# GPSclock.net
KiCad netlist of a schematic drawn in EasyEDA Pro
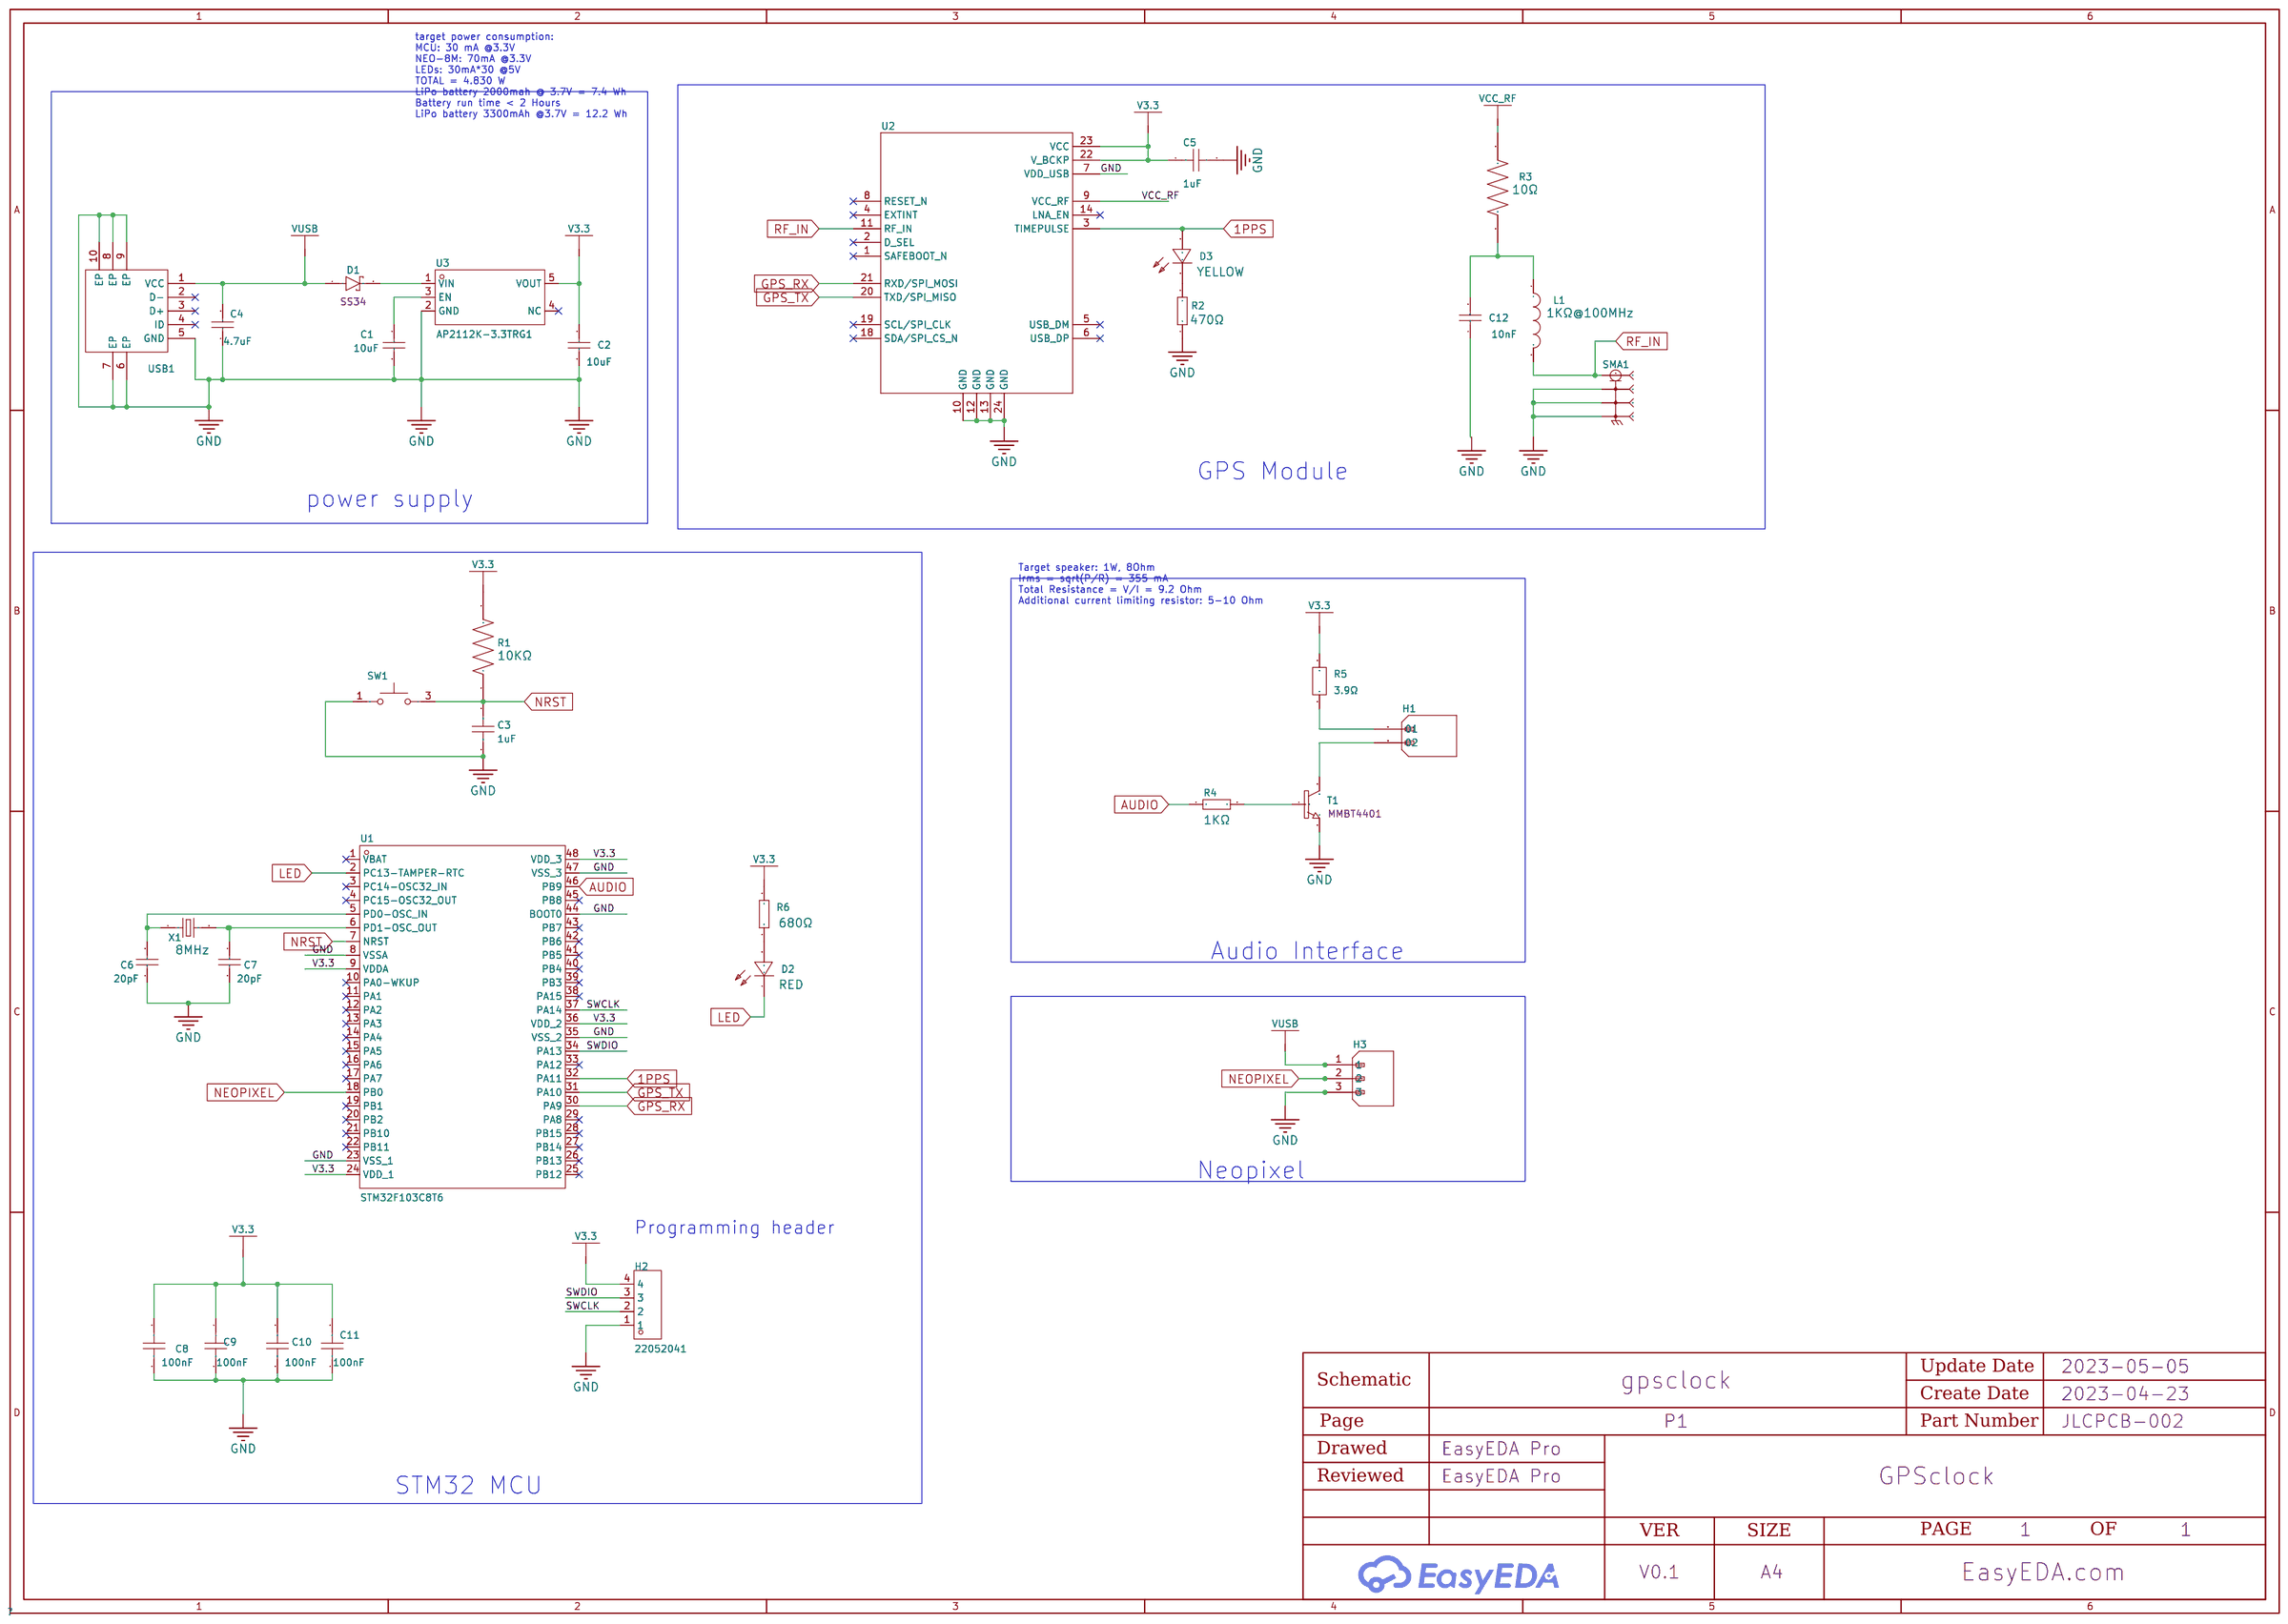
[diagram p0: schematic sheet]

(export (version "E")
  (design (tool "Eeschema 10.0.6"))
  (components
    (comp (ref "C1")
      (value "10uF")
      (footprint "easyedapro:C1206")
      (fields
        (field (name "Manufacturer Part") "CL31A106KBHNNNE")
        (field (name "Manufacturer") "SAMSUNG(三星)")
      )
      (libsource (lib "easyedapro") (part "CL31A106KBHNNNE"))
    )
    (comp (ref "C2")
      (value "10uF")
      (footprint "easyedapro:C1206")
      (fields
        (field (name "Manufacturer Part") "CL31A106KBHNNNE")
        (field (name "Manufacturer") "SAMSUNG(三星)")
      )
      (libsource (lib "easyedapro") (part "CL31A106KBHNNNE"))
    )
    (comp (ref "C3")
      (value "1uF")
      (footprint "easyedapro:C1206")
      (fields
        (field (name "Manufacturer Part") "CL31B105KBHNNNE")
        (field (name "Manufacturer") "SAMSUNG(三星)")
        (field (name "Tolerance") "±10%")
      )
      (libsource (lib "easyedapro") (part "CL31B105KBHNNNE"))
    )
    (comp (ref "C4")
      (value "4.7uF")
      (footprint "easyedapro:C0603")
      (fields
        (field (name "Manufacturer Part") "CL10A475KO8NNNC")
        (field (name "Manufacturer") "SAMSUNG(三星)")
        (field (name "Tolerance") "±10%")
      )
      (libsource (lib "easyedapro") (part "CL10A475KO8NNNC"))
    )
    (comp (ref "C5")
      (value "1uF")
      (footprint "easyedapro:C1206")
      (fields
        (field (name "Manufacturer Part") "CL31B105KBHNNNE")
        (field (name "Manufacturer") "SAMSUNG(三星)")
        (field (name "Tolerance") "±10%")
      )
      (libsource (lib "easyedapro") (part "CL31B105KBHNNNE"))
    )
    (comp (ref "C6")
      (value "20pF")
      (footprint "easyedapro:C0603")
      (fields
        (field (name "Manufacturer Part") "CL10C200JB8NNNC")
        (field (name "Manufacturer") "SAMSUNG(三星)")
        (field (name "Tolerance") "±5%")
      )
      (libsource (lib "easyedapro") (part "CL10C200JB8NNNC"))
    )
    (comp (ref "C7")
      (value "20pF")
      (footprint "easyedapro:C0603")
      (fields
        (field (name "Manufacturer Part") "CL10C200JB8NNNC")
        (field (name "Manufacturer") "SAMSUNG(三星)")
        (field (name "Tolerance") "±5%")
      )
      (libsource (lib "easyedapro") (part "CL10C200JB8NNNC"))
    )
    (comp (ref "C8")
      (value "100nF")
      (footprint "easyedapro:C0603")
      (fields
        (field (name "Manufacturer Part") "CC0603KRX7R9BB104")
        (field (name "Manufacturer") "YAGEO(国巨)")
        (field (name "Tolerance") "±10%")
      )
      (libsource (lib "easyedapro") (part "CC0603KRX7R9BB104"))
    )
    (comp (ref "C9")
      (value "100nF")
      (footprint "easyedapro:C0603")
      (fields
        (field (name "Manufacturer Part") "CC0603KRX7R9BB104")
        (field (name "Manufacturer") "YAGEO(国巨)")
        (field (name "Tolerance") "±10%")
      )
      (libsource (lib "easyedapro") (part "CC0603KRX7R9BB104"))
    )
    (comp (ref "C10")
      (value "100nF")
      (footprint "easyedapro:C0603")
      (fields
        (field (name "Manufacturer Part") "CC0603KRX7R9BB104")
        (field (name "Manufacturer") "YAGEO(国巨)")
        (field (name "Tolerance") "±10%")
      )
      (libsource (lib "easyedapro") (part "CC0603KRX7R9BB104"))
    )
    (comp (ref "C11")
      (value "100nF")
      (footprint "easyedapro:C0603")
      (fields
        (field (name "Manufacturer Part") "CC0603KRX7R9BB104")
        (field (name "Manufacturer") "YAGEO(国巨)")
        (field (name "Tolerance") "±10%")
      )
      (libsource (lib "easyedapro") (part "CC0603KRX7R9BB104"))
    )
    (comp (ref "C12")
      (value "10nF")
      (footprint "easyedapro:C0805")
      (fields
        (field (name "Manufacturer Part") "CL21B103KBANNNC")
        (field (name "Manufacturer") "SAMSUNG(三星)")
        (field (name "Tolerance") "±10%")
      )
      (libsource (lib "easyedapro") (part "CL21B103KBANNNC"))
    )
    (comp (ref "D1")
      (value "~")
      (footprint "easyedapro:SODFL3718X102N")
      (description "SS34")
      (fields
        (field (name "Manufacturer Part") "SS34LWH")
        (field (name "Manufacturer") "Taiwan Semiconductor Corporation")
      )
      (libsource (lib "easyedapro") (part "SS34LWH_"))
    )
    (comp (ref "D2")
      (value "RED")
      (footprint "easyedapro:LED_APHD1608LVBC/D")
      (fields (field (name "Manufacturer Part") "APTD1608LSURCK") (field (name "Manufacturer") "Kingbright"))
      (libsource (lib "easyedapro") (part "APTD1608LSURCK"))
    )
    (comp (ref "D3")
      (value "YELLOW")
      (footprint "easyedapro:LED_APHD1608LVBC/D")
      (fields (field (name "Manufacturer Part") "APTD1608LSYCK") (field (name "Manufacturer") "Kingbright"))
      (libsource (lib "easyedapro") (part "APTD1608LSYCK"))
    )
    (comp (ref "H1")
      (value "~")
      (footprint "easyedapro:WURTH_61300211121")
      (fields
        (field (name "Manufacturer Part") "61300211121")
        (field (name "Manufacturer") "Würth Elektronik")
      )
      (libsource (lib "easyedapro") (part "61300211121_"))
    )
    (comp (ref "H2")
      (value "22052041")
      (footprint "easyedapro:HDR-TH_4P-P2.54-H-M-W9.5")
      (fields (field (name "Manufacturer") "MOLEX"))
      (libsource (lib "easyedapro") (part "22052041"))
    )
    (comp (ref "H3")
      (value "~")
      (footprint "easyedapro:AMPHENOL_G800W305018EU")
      (fields (field (name "Manufacturer Part") "G800W305018EU") (field (name "Manufacturer") "AMPHENOL"))
      (libsource (lib "easyedapro") (part "G800W305018EU_"))
    )
    (comp (ref "L1")
      (value "1KΩ@100MHz")
      (footprint "easyedapro:BEADC1005X55N")
      (fields
        (field (name "Manufacturer Part") "BLM15HG102BH1D")
        (field (name "Manufacturer") "Murata Electronics")
      )
      (libsource (lib "easyedapro") (part "BLM15HG102BH1D_"))
    )
    (comp (ref "R1")
      (value "10KΩ")
      (footprint "easyedapro:RES_ERA8AEB103V")
      (libsource (lib "easyedapro") (part "ERA8AEB103V_"))
    )
    (comp (ref "R2")
      (value "470Ω")
      (footprint "easyedapro:R0603_NEW")
      (fields (field (name "Manufacturer Part") "RC0603FR-13470RL") (field (name "Manufacturer") "YAGEO"))
      (libsource (lib "easyedapro") (part "RC0603FR-13470RL_"))
    )
    (comp (ref "R3")
      (value "10Ω")
      (footprint "easyedapro:RESC2012X60N")
      (fields (field (name "Manufacturer Part") "SR0805FR-4710RL") (field (name "Manufacturer") "YAGEO"))
      (libsource (lib "easyedapro") (part "SR0805FR-4710RL_"))
    )
    (comp (ref "R4")
      (value "1KΩ")
      (footprint "easyedapro:0603")
      (fields (field (name "Manufacturer Part") "RC0603FR-101KL") (field (name "Manufacturer") "YAGEO"))
      (libsource (lib "easyedapro") (part "RC0603FR-101KL_"))
    )
    (comp (ref "R5")
      (value "3.9Ω")
      (footprint "easyedapro:RES-TH_BD4.5-L11.5-P15.50-D0.8")
      (fields
        (field (name "Manufacturer Part") "RSF100JR-73-3R9")
        (field (name "Manufacturer") "YAGEO(国巨)")
        (field (name "Tolerance") "±5%")
      )
      (libsource (lib "easyedapro") (part "RSF100JR-73-3R9"))
    )
    (comp (ref "R6")
      (value "680Ω")
      (footprint "easyedapro:0603")
      (fields (field (name "Manufacturer Part") "RC0603FR-13680RL") (field (name "Manufacturer") "YAGEO"))
      (libsource (lib "easyedapro") (part "RC0603FR-13680RL_"))
    )
    (comp (ref "SMA1")
      (value "~")
      (footprint "easyedapro:MOLEX_0734120110")
      (fields (field (name "Manufacturer Part") "0734120110") (field (name "Manufacturer") "MOLEX"))
      (libsource (lib "easyedapro") (part "0734120110_"))
    )
    (comp (ref "SW1")
      (value "~")
      (footprint "easyedapro:SW_800SP9B6M6RE")
      (fields (field (name "Manufacturer Part") "800SP9B6M6RE") (field (name "Manufacturer") "E-Switch"))
      (libsource (lib "easyedapro") (part "800SP9B6M6RE_"))
    )
    (comp (ref "T1")
      (value "~")
      (footprint "easyedapro:TRANS_MMBT4401")
      (description "MMBT4401")
      (fields
        (field (name "Manufacturer Part") "4530-MMBT4401CT-ND")
        (field (name "Manufacturer") "ANBON SEMICONDUCTOR LIMITED")
      )
      (libsource (lib "easyedapro") (part "MMBT4401_"))
    )
    (comp (ref "U1")
      (value "STM32F103C8T6")
      (footprint "easyedapro:LQFP-48_L7.0-W7.0-P0.50-LS9.0-BL")
      (fields (field (name "Manufacturer") "ST(意法半导体)"))
      (libsource (lib "easyedapro") (part "STM32F103C8T6"))
    )
    (comp (ref "U2")
      (value "~")
      (footprint "easyedapro:XCVR_NEO-M8N-0")
      (fields (field (name "Manufacturer Part") "NEO-M8N-0") (field (name "Manufacturer") "U-BLOX"))
      (libsource (lib "easyedapro") (part "NEO-M8N-0_"))
    )
    (comp (ref "U3")
      (value "AP2112K-3.3TRG1")
      (footprint "easyedapro:SOT-25-5_L2.9-W1.6-P0.95-LS2.8-BL")
      (fields (field (name "Manufacturer") "DIODES(美台)"))
      (libsource (lib "easyedapro") (part "AP2112K-3.3TRG1"))
    )
    (comp (ref "USB1")
      (value "1050170001")
      (footprint "easyedapro:MICRO-USB-SMD_105017-0001")
      (fields (field (name "Manufacturer") "MOLEX"))
      (libsource (lib "easyedapro") (part "105017-0001"))
    )
    (comp (ref "X1")
      (value "8MHz")
      (fields (field (name "Manufacturer Part") "ECS-80-18-5PX-TR") (field (name "Manufacturer") "ECS inc"))
      (libsource (lib "easyedapro") (part "ECS-80-18-5PX-TR_"))
    )
  )
  (nets
    (net (code "1") (name "/SWCLK") (class "Default")
      (node (ref "H2") (pin "2") (pinfunction "2_2") (pintype "input"))
      (node (ref "U1") (pin "37") (pinfunction "PA14_37") (pintype "input"))
    )
    (net (code "2") (name "/SWDIO") (class "Default")
      (node (ref "H2") (pin "3") (pinfunction "3_3") (pintype "input"))
      (node (ref "U1") (pin "34") (pinfunction "PA13_34") (pintype "input"))
    )
    (net (code "3") (name "1PPS") (class "Default")
      (node (ref "D3") (pin "2") (pinfunction "2_2") (pintype "input"))
      (node (ref "U1") (pin "32") (pinfunction "PA11_32") (pintype "input"))
      (node (ref "U2") (pin "3") (pinfunction "TIMEPULSE_3") (pintype "output"))
    )
    (net (code "4") (name "AUDIO") (class "Default")
      (node (ref "R4") (pin "1") (pinfunction "1_1") (pintype "input"))
      (node (ref "U1") (pin "46") (pinfunction "PB9_46") (pintype "input"))
    )
    (net (code "5") (name "GND") (class "Default")
      (node (ref "C1") (pin "1") (pinfunction "1_1") (pintype "input"))
      (node (ref "C10") (pin "1") (pinfunction "1_1") (pintype "input"))
      (node (ref "C11") (pin "1") (pinfunction "1_1") (pintype "input"))
      (node (ref "C12") (pin "1") (pinfunction "1_1") (pintype "input"))
      (node (ref "C2") (pin "1") (pinfunction "1_1") (pintype "input"))
      (node (ref "C3") (pin "1") (pinfunction "1_1") (pintype "input"))
      (node (ref "C4") (pin "1") (pinfunction "1_1") (pintype "input"))
      (node (ref "C5") (pin "2") (pinfunction "2_2") (pintype "input"))
      (node (ref "C6") (pin "1") (pinfunction "1_1") (pintype "input"))
      (node (ref "C7") (pin "2") (pinfunction "2_2") (pintype "input"))
      (node (ref "C8") (pin "1") (pinfunction "1_1") (pintype "input"))
      (node (ref "C9") (pin "2") (pinfunction "2_2") (pintype "input"))
      (node (ref "H2") (pin "1") (pinfunction "1_1") (pintype "input"))
      (node (ref "H3") (pin "3") (pinfunction "3_3") (pintype "input"))
      (node (ref "R2") (pin "1") (pinfunction "1_1") (pintype "input"))
      (node (ref "SMA1") (pin "2") (pinfunction "GND_2") (pintype "input"))
      (node (ref "SMA1") (pin "3") (pinfunction "GND_3") (pintype "input"))
      (node (ref "SMA1") (pin "4") (pinfunction "GND_4") (pintype "input"))
      (node (ref "SW1") (pin "1") (pinfunction "1_1") (pintype "input"))
      (node (ref "T1") (pin "2") (pinfunction "E_2") (pintype "input"))
      (node (ref "U1") (pin "23") (pinfunction "VSS_1_23") (pintype "input"))
      (node (ref "U1") (pin "35") (pinfunction "VSS_2_35") (pintype "input"))
      (node (ref "U1") (pin "44") (pinfunction "BOOT0_44") (pintype "input"))
      (node (ref "U1") (pin "47") (pinfunction "VSS_3_47") (pintype "input"))
      (node (ref "U1") (pin "8") (pinfunction "VSSA_8") (pintype "input"))
      (node (ref "U2") (pin "10") (pinfunction "GND_10") (pintype "input"))
      (node (ref "U2") (pin "12") (pinfunction "GND_12") (pintype "input"))
      (node (ref "U2") (pin "13") (pinfunction "GND_13") (pintype "input"))
      (node (ref "U2") (pin "24") (pinfunction "GND_24") (pintype "input"))
      (node (ref "U2") (pin "7") (pinfunction "VDD_USB_7") (pintype "input"))
      (node (ref "U3") (pin "2") (pinfunction "GND_2") (pintype "input"))
      (node (ref "USB1") (pin "10") (pinfunction "EP_10") (pintype "input"))
      (node (ref "USB1") (pin "5") (pinfunction "GND_5") (pintype "input"))
      (node (ref "USB1") (pin "6") (pinfunction "EP_6") (pintype "input"))
      (node (ref "USB1") (pin "7") (pinfunction "EP_7") (pintype "input"))
      (node (ref "USB1") (pin "8") (pinfunction "EP_8") (pintype "input"))
      (node (ref "USB1") (pin "9") (pinfunction "EP_9") (pintype "input"))
    )
    (net (code "6") (name "GPS_RX") (class "Default")
      (node (ref "U1") (pin "30") (pinfunction "PA9_30") (pintype "input"))
      (node (ref "U2") (pin "21") (pinfunction "RXD/SPI_MOSI_21") (pintype "input"))
    )
    (net (code "7") (name "GPS_TX") (class "Default")
      (node (ref "U1") (pin "31") (pinfunction "PA10_31") (pintype "input"))
      (node (ref "U2") (pin "20") (pinfunction "TXD/SPI_MISO_20") (pintype "output"))
    )
    (net (code "8") (name "LED") (class "Default")
      (node (ref "D2") (pin "1") (pinfunction "1_1") (pintype "input"))
      (node (ref "U1") (pin "2") (pinfunction "PC13-TAMPER-RTC_2") (pintype "input"))
    )
    (net (code "9") (name "NEOPIXEL") (class "Default")
      (node (ref "H3") (pin "2") (pinfunction "2_2") (pintype "input"))
      (node (ref "U1") (pin "18") (pinfunction "PB0_18") (pintype "input"))
    )
    (net (code "10") (name "NRST") (class "Default")
      (node (ref "C3") (pin "2") (pinfunction "2_2") (pintype "input"))
      (node (ref "R1") (pin "1") (pinfunction "1_1") (pintype "input"))
      (node (ref "SW1") (pin "3") (pinfunction "3_3") (pintype "input"))
      (node (ref "U1") (pin "7") (pinfunction "NRST_7") (pintype "input"))
    )
    (net (code "11") (name "Net-(C12-Pad2)") (class "Default")
      (node (ref "C12") (pin "2") (pinfunction "2_2") (pintype "input"))
      (node (ref "L1") (pin "1") (pinfunction "1_1") (pintype "input"))
      (node (ref "R3") (pin "1") (pinfunction "1_1") (pintype "input"))
    )
    (net (code "12") (name "Net-(D1-K)") (class "Default")
      (node (ref "D1") (pin "C") (pinfunction "K_C") (pintype "input"))
      (node (ref "U3") (pin "1") (pinfunction "VIN_1") (pintype "input"))
    )
    (net (code "13") (name "Net-(D2-Pad2)") (class "Default")
      (node (ref "D2") (pin "2") (pinfunction "2_2") (pintype "input"))
      (node (ref "R6") (pin "1") (pinfunction "1_1") (pintype "input"))
    )
    (net (code "14") (name "Net-(D3-Pad1)") (class "Default")
      (node (ref "D3") (pin "1") (pinfunction "1_1") (pintype "input"))
      (node (ref "R2") (pin "2") (pinfunction "2_2") (pintype "input"))
    )
    (net (code "15") (name "Net-(H1-Pad01)") (class "Default")
      (node (ref "H1") (pin "01") (pinfunction "01_01") (pintype "input"))
      (node (ref "R5") (pin "1") (pinfunction "1_1") (pintype "input"))
    )
    (net (code "16") (name "Net-(T1-B)") (class "Default")
      (node (ref "R4") (pin "2") (pinfunction "2_2") (pintype "input"))
      (node (ref "T1") (pin "1") (pinfunction "B_1") (pintype "input"))
    )
    (net (code "17") (name "Net-(T1-C)") (class "Default")
      (node (ref "H1") (pin "02") (pinfunction "02_02") (pintype "input"))
      (node (ref "T1") (pin "3") (pinfunction "C_3") (pintype "input"))
    )
    (net (code "18") (name "Net-(U1-PD0-OSC_IN)") (class "Default")
      (node (ref "C6") (pin "2") (pinfunction "2_2") (pintype "input"))
      (node (ref "U1") (pin "5") (pinfunction "PD0-OSC_IN_5") (pintype "input"))
      (node (ref "X1") (pin "1") (pinfunction "1_1") (pintype "input"))
    )
    (net (code "19") (name "Net-(U1-PD1-OSC_OUT)") (class "Default")
      (node (ref "C7") (pin "1") (pinfunction "1_1") (pintype "input"))
      (node (ref "U1") (pin "6") (pinfunction "PD1-OSC_OUT_6") (pintype "input"))
      (node (ref "X1") (pin "2") (pinfunction "2_2") (pintype "input"))
    )
    (net (code "20") (name "Net-(U3-EN)") (class "Default")
      (node (ref "C1") (pin "2") (pinfunction "2_2") (pintype "input"))
      (node (ref "U3") (pin "3") (pinfunction "EN_3") (pintype "input"))
    )
    (net (code "21") (name "RF_IN") (class "Default")
      (node (ref "L1") (pin "2") (pinfunction "2_2") (pintype "input"))
      (node (ref "SMA1") (pin "1") (pinfunction "SIG_1") (pintype "input"))
      (node (ref "U2") (pin "11") (pinfunction "RF_IN_11") (pintype "input"))
    )
    (net (code "22") (name "V3.3") (class "Default")
      (node (ref "C10") (pin "2") (pinfunction "2_2") (pintype "input"))
      (node (ref "C11") (pin "2") (pinfunction "2_2") (pintype "input"))
      (node (ref "C2") (pin "2") (pinfunction "2_2") (pintype "input"))
      (node (ref "C5") (pin "1") (pinfunction "1_1") (pintype "input"))
      (node (ref "C8") (pin "2") (pinfunction "2_2") (pintype "input"))
      (node (ref "C9") (pin "1") (pinfunction "1_1") (pintype "input"))
      (node (ref "H2") (pin "4") (pinfunction "4_4") (pintype "input"))
      (node (ref "R1") (pin "2") (pinfunction "2_2") (pintype "input"))
      (node (ref "R5") (pin "2") (pinfunction "2_2") (pintype "input"))
      (node (ref "R6") (pin "2") (pinfunction "2_2") (pintype "input"))
      (node (ref "U1") (pin "24") (pinfunction "VDD_1_24") (pintype "input"))
      (node (ref "U1") (pin "36") (pinfunction "VDD_2_36") (pintype "input"))
      (node (ref "U1") (pin "48") (pinfunction "VDD_3_48") (pintype "input"))
      (node (ref "U1") (pin "9") (pinfunction "VDDA_9") (pintype "input"))
      (node (ref "U2") (pin "22") (pinfunction "V_BCKP_22") (pintype "input"))
      (node (ref "U2") (pin "23") (pinfunction "VCC_23") (pintype "input"))
      (node (ref "U3") (pin "5") (pinfunction "VOUT_5") (pintype "input"))
    )
    (net (code "23") (name "VCC_RF") (class "Default")
      (node (ref "R3") (pin "2") (pinfunction "2_2") (pintype "input"))
      (node (ref "U2") (pin "9") (pinfunction "VCC_RF_9") (pintype "output"))
    )
    (net (code "24") (name "VUSB") (class "Default")
      (node (ref "C4") (pin "2") (pinfunction "2_2") (pintype "input"))
      (node (ref "D1") (pin "A") (pinfunction "A_A") (pintype "input"))
      (node (ref "H3") (pin "1") (pinfunction "1_1") (pintype "input"))
      (node (ref "USB1") (pin "1") (pinfunction "VCC_1") (pintype "input"))
    )
    (net (code "25") (name "unconnected-(U1-PA0-WKUP-Pad10)") (class "Default")
      (node (ref "U1") (pin "10") (pinfunction "PA0-WKUP_10") (pintype "input+no_connect"))
    )
    (net (code "26") (name "unconnected-(U1-PA1-Pad11)") (class "Default")
      (node (ref "U1") (pin "11") (pinfunction "PA1_11") (pintype "input+no_connect"))
    )
    (net (code "27") (name "unconnected-(U1-PA2-Pad12)") (class "Default")
      (node (ref "U1") (pin "12") (pinfunction "PA2_12") (pintype "input+no_connect"))
    )
    (net (code "28") (name "unconnected-(U1-PA3-Pad13)") (class "Default")
      (node (ref "U1") (pin "13") (pinfunction "PA3_13") (pintype "input+no_connect"))
    )
    (net (code "29") (name "unconnected-(U1-PA4-Pad14)") (class "Default")
      (node (ref "U1") (pin "14") (pinfunction "PA4_14") (pintype "input+no_connect"))
    )
    (net (code "30") (name "unconnected-(U1-PA5-Pad15)") (class "Default")
      (node (ref "U1") (pin "15") (pinfunction "PA5_15") (pintype "input+no_connect"))
    )
    (net (code "31") (name "unconnected-(U1-PA6-Pad16)") (class "Default")
      (node (ref "U1") (pin "16") (pinfunction "PA6_16") (pintype "input+no_connect"))
    )
    (net (code "32") (name "unconnected-(U1-PA7-Pad17)") (class "Default")
      (node (ref "U1") (pin "17") (pinfunction "PA7_17") (pintype "input+no_connect"))
    )
    (net (code "33") (name "unconnected-(U1-PA8-Pad29)") (class "Default")
      (node (ref "U1") (pin "29") (pinfunction "PA8_29") (pintype "input+no_connect"))
    )
    (net (code "34") (name "unconnected-(U1-PA12-Pad33)") (class "Default")
      (node (ref "U1") (pin "33") (pinfunction "PA12_33") (pintype "input+no_connect"))
    )
    (net (code "35") (name "unconnected-(U1-PA15-Pad38)") (class "Default")
      (node (ref "U1") (pin "38") (pinfunction "PA15_38") (pintype "input+no_connect"))
    )
    (net (code "36") (name "unconnected-(U1-PB1-Pad19)") (class "Default")
      (node (ref "U1") (pin "19") (pinfunction "PB1_19") (pintype "input+no_connect"))
    )
    (net (code "37") (name "unconnected-(U1-PB2-Pad20)") (class "Default")
      (node (ref "U1") (pin "20") (pinfunction "PB2_20") (pintype "input+no_connect"))
    )
    (net (code "38") (name "unconnected-(U1-PB3-Pad39)") (class "Default")
      (node (ref "U1") (pin "39") (pinfunction "PB3_39") (pintype "input+no_connect"))
    )
    (net (code "39") (name "unconnected-(U1-PB4-Pad40)") (class "Default")
      (node (ref "U1") (pin "40") (pinfunction "PB4_40") (pintype "input+no_connect"))
    )
    (net (code "40") (name "unconnected-(U1-PB5-Pad41)") (class "Default")
      (node (ref "U1") (pin "41") (pinfunction "PB5_41") (pintype "input+no_connect"))
    )
    (net (code "41") (name "unconnected-(U1-PB6-Pad42)") (class "Default")
      (node (ref "U1") (pin "42") (pinfunction "PB6_42") (pintype "input+no_connect"))
    )
    (net (code "42") (name "unconnected-(U1-PB7-Pad43)") (class "Default")
      (node (ref "U1") (pin "43") (pinfunction "PB7_43") (pintype "input+no_connect"))
    )
    (net (code "43") (name "unconnected-(U1-PB8-Pad45)") (class "Default")
      (node (ref "U1") (pin "45") (pinfunction "PB8_45") (pintype "input+no_connect"))
    )
    (net (code "44") (name "unconnected-(U1-PB10-Pad21)") (class "Default")
      (node (ref "U1") (pin "21") (pinfunction "PB10_21") (pintype "input+no_connect"))
    )
    (net (code "45") (name "unconnected-(U1-PB11-Pad22)") (class "Default")
      (node (ref "U1") (pin "22") (pinfunction "PB11_22") (pintype "input+no_connect"))
    )
    (net (code "46") (name "unconnected-(U1-PB12-Pad25)") (class "Default")
      (node (ref "U1") (pin "25") (pinfunction "PB12_25") (pintype "input+no_connect"))
    )
    (net (code "47") (name "unconnected-(U1-PB13-Pad26)") (class "Default")
      (node (ref "U1") (pin "26") (pinfunction "PB13_26") (pintype "input+no_connect"))
    )
    (net (code "48") (name "unconnected-(U1-PB14-Pad27)") (class "Default")
      (node (ref "U1") (pin "27") (pinfunction "PB14_27") (pintype "input+no_connect"))
    )
    (net (code "49") (name "unconnected-(U1-PB15-Pad28)") (class "Default")
      (node (ref "U1") (pin "28") (pinfunction "PB15_28") (pintype "input+no_connect"))
    )
    (net (code "50") (name "unconnected-(U1-PC14-OSC32_IN-Pad3)") (class "Default")
      (node (ref "U1") (pin "3") (pinfunction "PC14-OSC32_IN_3") (pintype "input+no_connect"))
    )
    (net (code "51") (name "unconnected-(U1-PC15-OSC32_OUT-Pad4)") (class "Default")
      (node (ref "U1") (pin "4") (pinfunction "PC15-OSC32_OUT_4") (pintype "input+no_connect"))
    )
    (net (code "52") (name "unconnected-(U1-VBAT-Pad1)") (class "Default")
      (node (ref "U1") (pin "1") (pinfunction "VBAT_1") (pintype "input+no_connect"))
    )
    (net (code "53") (name "unconnected-(U2-D_SEL-Pad2)") (class "Default")
      (node (ref "U2") (pin "2") (pinfunction "D_SEL_2") (pintype "input+no_connect"))
    )
    (net (code "54") (name "unconnected-(U2-EXTINT-Pad4)") (class "Default")
      (node (ref "U2") (pin "4") (pinfunction "EXTINT_4") (pintype "input+no_connect"))
    )
    (net (code "55") (name "unconnected-(U2-LNA_EN-Pad14)") (class "Default")
      (node (ref "U2") (pin "14") (pinfunction "LNA_EN_14") (pintype "output+no_connect"))
    )
    (net (code "56") (name "unconnected-(U2-RESET_N-Pad8)") (class "Default")
      (node (ref "U2") (pin "8") (pinfunction "RESET_N_8") (pintype "input+no_connect"))
    )
    (net (code "57") (name "unconnected-(U2-SAFEBOOT_N-Pad1)") (class "Default")
      (node (ref "U2") (pin "1") (pinfunction "SAFEBOOT_N_1") (pintype "input+no_connect"))
    )
    (net (code "58") (name "unconnected-(U2-SCL{slash}SPI_CLK-Pad19)") (class "Default")
      (node (ref "U2") (pin "19") (pinfunction "SCL/SPI_CLK_19") (pintype "input+no_connect"))
    )
    (net (code "59") (name "unconnected-(U2-SDA{slash}SPI_CS_N-Pad18)") (class "Default")
      (node (ref "U2") (pin "18") (pinfunction "SDA/SPI_CS_N_18") (pintype "input+no_connect"))
    )
    (net (code "60") (name "unconnected-(U2-USB_DM-Pad5)") (class "Default")
      (node (ref "U2") (pin "5") (pinfunction "USB_DM_5") (pintype "input+no_connect"))
    )
    (net (code "61") (name "unconnected-(U2-USB_DP-Pad6)") (class "Default")
      (node (ref "U2") (pin "6") (pinfunction "USB_DP_6") (pintype "input+no_connect"))
    )
    (net (code "62") (name "unconnected-(U3-NC-Pad4)") (class "Default")
      (node (ref "U3") (pin "4") (pinfunction "NC_4") (pintype "input+no_connect"))
    )
    (net (code "63") (name "unconnected-(USB1-D+-Pad3)") (class "Default")
      (node (ref "USB1") (pin "3") (pinfunction "D+_3") (pintype "input+no_connect"))
    )
    (net (code "64") (name "unconnected-(USB1-D--Pad2)") (class "Default")
      (node (ref "USB1") (pin "2") (pinfunction "D-_2") (pintype "input+no_connect"))
    )
    (net (code "65") (name "unconnected-(USB1-ID-Pad4)") (class "Default")
      (node (ref "USB1") (pin "4") (pinfunction "ID_4") (pintype "input+no_connect"))
    )
  )
)
